# Shunt_Amp_Meter.net
KiCad netlist of a schematic drawn in EAGLE
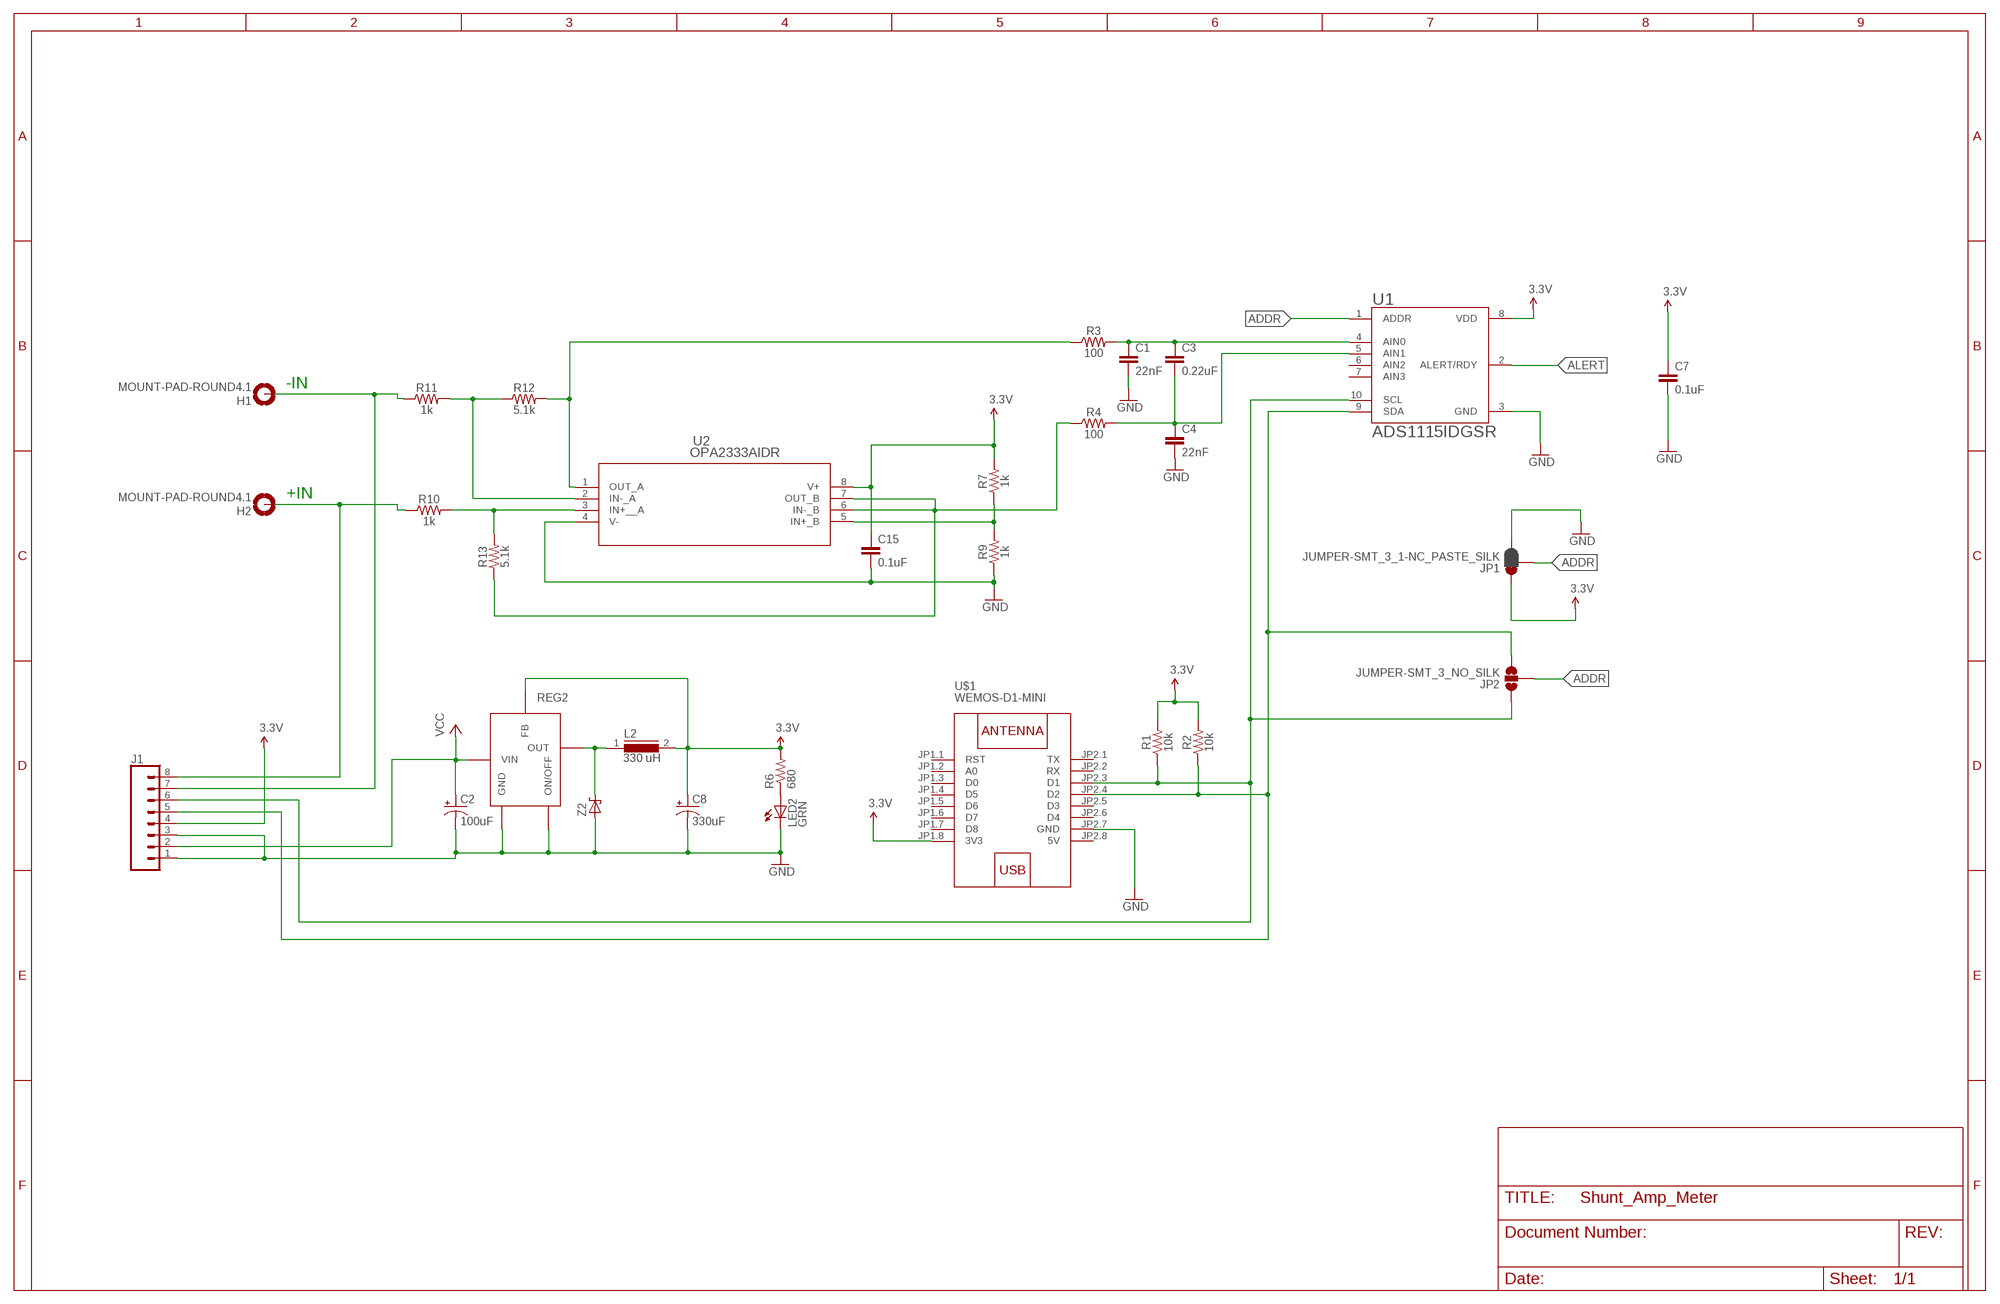
[diagram p0: schematic, sheet 1]

(export (version "E")
  (design (tool "Eeschema 10.0.6"))
  (components
    (comp (ref "C1")
      (value "22nF")
      (footprint "eagle-import:0603")
      (libsource (lib "eagle-import") (part "22NF/22,000PF-0603-50V-10%"))
    )
    (comp (ref "C2")
      (value "100uF")
      (footprint "eagle-import:F_CAP")
      (libsource (lib "eagle-import") (part "CAP_POLF"))
    )
    (comp (ref "C3")
      (value "0.22uF")
      (footprint "eagle-import:0603")
      (libsource (lib "eagle-import") (part "0.22UF-0603-25V-10%"))
    )
    (comp (ref "C4")
      (value "22nF")
      (footprint "eagle-import:0603")
      (libsource (lib "eagle-import") (part "22NF/22,000PF-0603-50V-10%"))
    )
    (comp (ref "C7")
      (value "0.1uF")
      (footprint "eagle-import:0603")
      (libsource (lib "eagle-import") (part "0.1UF-0603-25V-5%"))
    )
    (comp (ref "C8")
      (value "330uF")
      (footprint "eagle-import:F_CAP")
      (libsource (lib "eagle-import") (part "CAP_POLF"))
    )
    (comp (ref "C15")
      (value "0.1uF")
      (footprint "eagle-import:0603")
      (libsource (lib "eagle-import") (part "0.1UF-0603-25V-(+80/-20%)"))
    )
    (comp (ref "H1")
      (value "MOUNT-PAD-ROUND4.1")
      (footprint "eagle-import:4,1-PAD")
      (libsource (lib "eagle-import") (part "MOUNT-PAD-ROUND4.1"))
    )
    (comp (ref "H2")
      (value "MOUNT-PAD-ROUND4.1")
      (footprint "eagle-import:4,1-PAD")
      (libsource (lib "eagle-import") (part "MOUNT-PAD-ROUND4.1"))
    )
    (comp (ref "J1")
      (value "CONN_08\"")
      (footprint "eagle-import:1X08")
      (libsource (lib "eagle-import") (part "CONN_08{dblquote}"))
    )
    (comp (ref "JP1")
      (value "JUMPER-SMT_3_1-NC_PASTE_SILK")
      (footprint "eagle-import:SMT-JUMPER_3_1-NC_PASTE_SILK")
      (libsource (lib "eagle-import") (part "JUMPER-SMT_3_1-NC_PASTE_SILK"))
    )
    (comp (ref "JP2")
      (value "JUMPER-SMT_3_NO_SILK")
      (footprint "eagle-import:SMT-JUMPER_3_NO_SILK")
      (libsource (lib "eagle-import") (part "JUMPER-SMT_3_NO_SILK"))
    )
    (comp (ref "L2")
      (value "330 uH")
      (footprint "eagle-import:DR125")
      (libsource (lib "eagle-import") (part "DR125"))
    )
    (comp (ref "LED2")
      (value "GRN")
      (footprint "eagle-import:0603_LED")
      (fields (field (name "MANF") "Avago Technologies"))
      (libsource (lib "eagle-import") (part "LED0603"))
    )
    (comp (ref "R1")
      (value "10k")
      (footprint "eagle-import:0603")
      (libsource (lib "eagle-import") (part "10KOHM-0603-1/10W-1%"))
    )
    (comp (ref "R2")
      (value "10k")
      (footprint "eagle-import:0603")
      (libsource (lib "eagle-import") (part "10KOHM-0603-1/10W-1%"))
    )
    (comp (ref "R3")
      (value "100")
      (footprint "eagle-import:0603")
      (libsource (lib "eagle-import") (part "100OHM-0603-1/4W-5%"))
    )
    (comp (ref "R4")
      (value "100")
      (footprint "eagle-import:0603")
      (libsource (lib "eagle-import") (part "100OHM-0603-1/4W-5%"))
    )
    (comp (ref "R6")
      (value "680")
      (footprint "eagle-import:0603_RESISTOR")
      (libsource (lib "eagle-import") (part "jkf_RESISTOR0603"))
    )
    (comp (ref "R7")
      (value "1k")
      (footprint "eagle-import:0603")
      (libsource (lib "eagle-import") (part "1KOHM-0603-1/10W-1%"))
    )
    (comp (ref "R9")
      (value "1k")
      (footprint "eagle-import:0603")
      (libsource (lib "eagle-import") (part "1KOHM-0603-1/10W-1%"))
    )
    (comp (ref "R10")
      (value "1k")
      (footprint "eagle-import:0603")
      (libsource (lib "eagle-import") (part "1KOHM-0603-1/10W-1%"))
    )
    (comp (ref "R11")
      (value "1k")
      (footprint "eagle-import:0603")
      (libsource (lib "eagle-import") (part "1KOHM-0603-1/10W-1%"))
    )
    (comp (ref "R12")
      (value "5.1k")
      (footprint "eagle-import:0603")
      (libsource (lib "eagle-import") (part "RESISTOR0603"))
    )
    (comp (ref "R13")
      (value "5.1k")
      (footprint "eagle-import:0603")
      (libsource (lib "eagle-import") (part "RESISTOR0603"))
    )
    (comp (ref "REG2")
      (value "TL2575")
      (footprint "eagle-import:TO-263-6")
      (fields (field (name "MANF") "Texas Instruments"))
      (libsource (lib "eagle-import") (part "TL2575"))
    )
    (comp (ref "U$1")
      (value "WEMOS-D1-MINI")
      (footprint "eagle-import:WEMOS-D1-MINI")
      (libsource (lib "eagle-import") (part "WEMOS-D1-MINI"))
    )
    (comp (ref "U1")
      (value "ADS1115IDGSR")
      (footprint "eagle-import:SOP50P490X110-10N")
      (fields (field (name "DIGI-KEY_PART_NUMBER") "296-38849-1-ND") (field (name "MF") "Texas Instruments"))
      (libsource (lib "eagle-import") (part "ADS1115IDGSR"))
    )
    (comp (ref "U2")
      (value "OPA2333AIDR")
      (footprint "eagle-import:D8")
      (libsource (lib "eagle-import") (part "OPA2333AIDR"))
    )
    (comp (ref "Z2")
      (value "SCHOTTKY_DIODE")
      (footprint "eagle-import:SMD_DIODE")
      (fields (field (name "MANF") "Diodes Inc"))
      (libsource (lib "eagle-import") (part "SCHOTTKY_DIODE"))
    )
  )
  (nets
    (net (code "1") (name "/5V") (class "Default")
      (node (ref "U$1") (pin "JP2.8") (pinfunction "5V_JP2.8") (pintype "power_in"))
    )
    (net (code "2") (name "3.3V") (class "Default")
      (node (ref "C15") (pin "1") (pinfunction "1_1") (pintype "passive"))
      (node (ref "C7") (pin "1") (pinfunction "1_1") (pintype "passive"))
      (node (ref "C8") (pin "+") (pinfunction "+_+") (pintype "passive"))
      (node (ref "J1") (pin "4") (pinfunction "4_4") (pintype "passive"))
      (node (ref "JP1") (pin "1") (pinfunction "1_1") (pintype "passive"))
      (node (ref "L2") (pin "2") (pinfunction "2_2") (pintype "passive"))
      (node (ref "R1") (pin "2") (pinfunction "2_2") (pintype "passive"))
      (node (ref "R2") (pin "2") (pinfunction "2_2") (pintype "passive"))
      (node (ref "R6") (pin "2") (pinfunction "2_2") (pintype "passive"))
      (node (ref "R7") (pin "2") (pinfunction "2_2") (pintype "passive"))
      (node (ref "REG2") (pin "4") (pinfunction "FB_4") (pintype "input"))
      (node (ref "U$1") (pin "JP1.8") (pinfunction "3V3_JP1.8") (pintype "power_in"))
      (node (ref "U1") (pin "8") (pinfunction "VDD_8") (pintype "power_in"))
      (node (ref "U2") (pin "8") (pinfunction "V+_8") (pintype "power_in"))
    )
    (net (code "3") (name "ADDR") (class "Default")
      (node (ref "JP1") (pin "2") (pinfunction "2_2") (pintype "passive"))
      (node (ref "JP2") (pin "2") (pinfunction "2_2") (pintype "passive"))
      (node (ref "U1") (pin "1") (pinfunction "ADDR_1") (pintype "input"))
    )
    (net (code "4") (name "ALERT") (class "Default")
      (node (ref "U1") (pin "2") (pinfunction "ALERT/RDY_2") (pintype "output"))
    )
    (net (code "5") (name "GND") (class "Default")
      (node (ref "C1") (pin "2") (pinfunction "2_2") (pintype "passive"))
      (node (ref "C15") (pin "2") (pinfunction "2_2") (pintype "passive"))
      (node (ref "C2") (pin "-") (pinfunction "-_-") (pintype "passive"))
      (node (ref "C4") (pin "2") (pinfunction "2_2") (pintype "passive"))
      (node (ref "C7") (pin "2") (pinfunction "2_2") (pintype "passive"))
      (node (ref "C8") (pin "-") (pinfunction "-_-") (pintype "passive"))
      (node (ref "J1") (pin "1") (pinfunction "1_1") (pintype "passive"))
      (node (ref "J1") (pin "3") (pinfunction "3_3") (pintype "passive"))
      (node (ref "JP1") (pin "3") (pinfunction "3_3") (pintype "passive"))
      (node (ref "LED2") (pin "C") (pinfunction "C_C") (pintype "passive"))
      (node (ref "R9") (pin "1") (pinfunction "1_1") (pintype "passive"))
      (node (ref "REG2") (pin "3") (pinfunction "GND_3") (pintype "power_in"))
      (node (ref "REG2") (pin "5") (pinfunction "ON/OFF_5") (pintype "input"))
      (node (ref "U$1") (pin "JP2.7") (pinfunction "GND_JP2.7") (pintype "power_in"))
      (node (ref "U1") (pin "3") (pinfunction "GND_3") (pintype "power_in"))
      (node (ref "U2") (pin "4") (pinfunction "V-_4") (pintype "power_in"))
      (node (ref "Z2") (pin "A") (pinfunction "A_A") (pintype "passive"))
    )
    (net (code "6") (name "Net-(H1-MOUNT)") (class "Default")
      (node (ref "H1") (pin "B4,1") (pinfunction "MOUNT_B4,1") (pintype "passive"))
      (node (ref "J1") (pin "7") (pinfunction "7_7") (pintype "passive"))
      (node (ref "R11") (pin "1") (pinfunction "1_1") (pintype "passive"))
    )
    (net (code "7") (name "Net-(H2-MOUNT)") (class "Default")
      (node (ref "H2") (pin "B4,1") (pinfunction "MOUNT_B4,1") (pintype "passive"))
      (node (ref "J1") (pin "8") (pinfunction "8_8") (pintype "passive"))
      (node (ref "R10") (pin "1") (pinfunction "1_1") (pintype "passive"))
    )
    (net (code "8") (name "Net-(LED2-PadA)") (class "Default")
      (node (ref "LED2") (pin "A") (pinfunction "A_A") (pintype "passive"))
      (node (ref "R6") (pin "1") (pinfunction "1_1") (pintype "passive"))
    )
    (net (code "9") (name "Net-(REG2-OUT)") (class "Default")
      (node (ref "L2") (pin "1") (pinfunction "1_1") (pintype "passive"))
      (node (ref "REG2") (pin "2") (pinfunction "OUT_2") (pintype "power_in"))
      (node (ref "Z2") (pin "C") (pinfunction "C_C") (pintype "passive"))
    )
    (net (code "10") (name "Net-(U$1-D1)") (class "Default")
      (node (ref "J1") (pin "6") (pinfunction "6_6") (pintype "passive"))
      (node (ref "JP2") (pin "1") (pinfunction "1_1") (pintype "passive"))
      (node (ref "R1") (pin "1") (pinfunction "1_1") (pintype "passive"))
      (node (ref "U$1") (pin "JP2.3") (pinfunction "D1_JP2.3") (pintype "bidirectional"))
      (node (ref "U1") (pin "10") (pinfunction "SCL_10") (pintype "input"))
    )
    (net (code "11") (name "Net-(U$1-D2)") (class "Default")
      (node (ref "J1") (pin "5") (pinfunction "5_5") (pintype "passive"))
      (node (ref "JP2") (pin "3") (pinfunction "3_3") (pintype "passive"))
      (node (ref "R2") (pin "1") (pinfunction "1_1") (pintype "passive"))
      (node (ref "U$1") (pin "JP2.4") (pinfunction "D2_JP2.4") (pintype "bidirectional"))
      (node (ref "U1") (pin "9") (pinfunction "SDA_9") (pintype "bidirectional"))
    )
    (net (code "12") (name "Net-(U1-AIN0)") (class "Default")
      (node (ref "C1") (pin "1") (pinfunction "1_1") (pintype "passive"))
      (node (ref "C3") (pin "1") (pinfunction "1_1") (pintype "passive"))
      (node (ref "R3") (pin "2") (pinfunction "2_2") (pintype "passive"))
      (node (ref "U1") (pin "4") (pinfunction "AIN0_4") (pintype "input"))
    )
    (net (code "13") (name "Net-(U1-AIN1)") (class "Default")
      (node (ref "C3") (pin "2") (pinfunction "2_2") (pintype "passive"))
      (node (ref "C4") (pin "1") (pinfunction "1_1") (pintype "passive"))
      (node (ref "R4") (pin "2") (pinfunction "2_2") (pintype "passive"))
      (node (ref "U1") (pin "5") (pinfunction "AIN1_5") (pintype "input"))
    )
    (net (code "14") (name "Net-(U2-IN+_B)") (class "Default")
      (node (ref "R7") (pin "1") (pinfunction "1_1") (pintype "passive"))
      (node (ref "R9") (pin "2") (pinfunction "2_2") (pintype "passive"))
      (node (ref "U2") (pin "5") (pinfunction "IN+_B_5") (pintype "input"))
    )
    (net (code "15") (name "Net-(U2-IN+__A)") (class "Default")
      (node (ref "R10") (pin "2") (pinfunction "2_2") (pintype "passive"))
      (node (ref "R13") (pin "2") (pinfunction "2_2") (pintype "passive"))
      (node (ref "U2") (pin "3") (pinfunction "IN+__A_3") (pintype "input"))
    )
    (net (code "16") (name "Net-(U2-IN-_A)") (class "Default")
      (node (ref "R11") (pin "2") (pinfunction "2_2") (pintype "passive"))
      (node (ref "R12") (pin "1") (pinfunction "1_1") (pintype "passive"))
      (node (ref "U2") (pin "2") (pinfunction "IN-_A_2") (pintype "input"))
    )
    (net (code "17") (name "Net-(U2-IN-_B)") (class "Default")
      (node (ref "R13") (pin "1") (pinfunction "1_1") (pintype "passive"))
      (node (ref "R4") (pin "1") (pinfunction "1_1") (pintype "passive"))
      (node (ref "U2") (pin "6") (pinfunction "IN-_B_6") (pintype "input"))
      (node (ref "U2") (pin "7") (pinfunction "OUT_B_7") (pintype "output"))
    )
    (net (code "18") (name "Net-(U2-OUT_A)") (class "Default")
      (node (ref "R12") (pin "2") (pinfunction "2_2") (pintype "passive"))
      (node (ref "R3") (pin "1") (pinfunction "1_1") (pintype "passive"))
      (node (ref "U2") (pin "1") (pinfunction "OUT_A_1") (pintype "output"))
    )
    (net (code "19") (name "VCC") (class "Default")
      (node (ref "C2") (pin "+") (pinfunction "+_+") (pintype "passive"))
      (node (ref "J1") (pin "2") (pinfunction "2_2") (pintype "passive"))
      (node (ref "REG2") (pin "1") (pinfunction "VIN_1") (pintype "power_in"))
    )
    (net (code "20") (name "unconnected-(U$1-A0-PadJP1.2)") (class "Default")
      (node (ref "U$1") (pin "JP1.2") (pinfunction "A0_JP1.2") (pintype "bidirectional"))
    )
    (net (code "21") (name "unconnected-(U$1-D0-PadJP1.3)") (class "Default")
      (node (ref "U$1") (pin "JP1.3") (pinfunction "D0_JP1.3") (pintype "bidirectional"))
    )
    (net (code "22") (name "unconnected-(U$1-D3-PadJP2.5)") (class "Default")
      (node (ref "U$1") (pin "JP2.5") (pinfunction "D3_JP2.5") (pintype "bidirectional"))
    )
    (net (code "23") (name "unconnected-(U$1-D4-PadJP2.6)") (class "Default")
      (node (ref "U$1") (pin "JP2.6") (pinfunction "D4_JP2.6") (pintype "bidirectional"))
    )
    (net (code "24") (name "unconnected-(U$1-D5-PadJP1.4)") (class "Default")
      (node (ref "U$1") (pin "JP1.4") (pinfunction "D5_JP1.4") (pintype "bidirectional"))
    )
    (net (code "25") (name "unconnected-(U$1-D6-PadJP1.5)") (class "Default")
      (node (ref "U$1") (pin "JP1.5") (pinfunction "D6_JP1.5") (pintype "bidirectional"))
    )
    (net (code "26") (name "unconnected-(U$1-D7-PadJP1.6)") (class "Default")
      (node (ref "U$1") (pin "JP1.6") (pinfunction "D7_JP1.6") (pintype "bidirectional"))
    )
    (net (code "27") (name "unconnected-(U$1-D8-PadJP1.7)") (class "Default")
      (node (ref "U$1") (pin "JP1.7") (pinfunction "D8_JP1.7") (pintype "bidirectional"))
    )
    (net (code "28") (name "unconnected-(U$1-RST-PadJP1.1)") (class "Default")
      (node (ref "U$1") (pin "JP1.1") (pinfunction "RST_JP1.1") (pintype "bidirectional"))
    )
    (net (code "29") (name "unconnected-(U$1-RX-PadJP2.2)") (class "Default")
      (node (ref "U$1") (pin "JP2.2") (pinfunction "RX_JP2.2") (pintype "bidirectional"))
    )
    (net (code "30") (name "unconnected-(U$1-TX-PadJP2.1)") (class "Default")
      (node (ref "U$1") (pin "JP2.1") (pinfunction "TX_JP2.1") (pintype "bidirectional"))
    )
    (net (code "31") (name "unconnected-(U1-AIN2-Pad6)") (class "Default")
      (node (ref "U1") (pin "6") (pinfunction "AIN2_6") (pintype "input"))
    )
    (net (code "32") (name "unconnected-(U1-AIN3-Pad7)") (class "Default")
      (node (ref "U1") (pin "7") (pinfunction "AIN3_7") (pintype "input"))
    )
  )
)
